# Schem.net
KiCad netlist of a schematic drawn in EAGLE
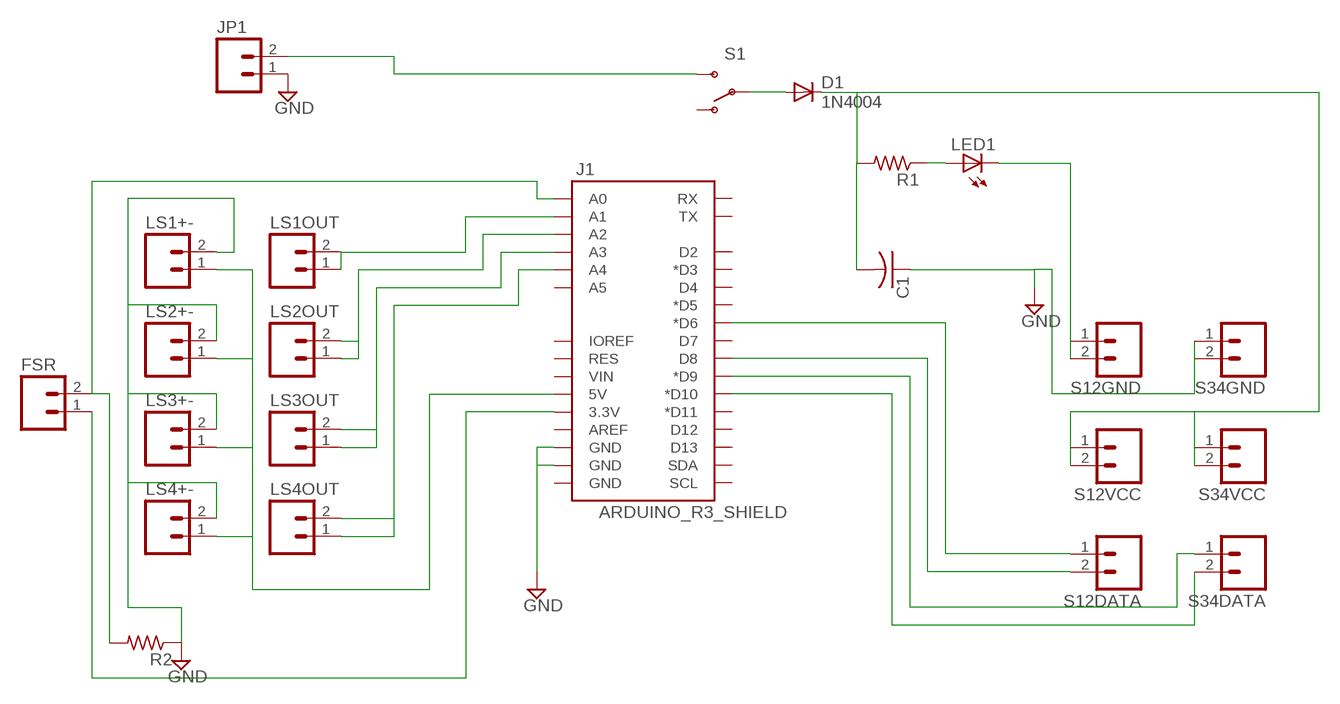
[diagram p0: schematic, sheet 1]

(export (version "E")
  (design (tool "Eeschema 10.0.6"))
  (components
    (comp (ref "C1")
      (value "C-US075-063X106")
      (footprint "eagle-import:C075-063X106")
      (libsource (lib "eagle-import") (part "C-US075-063X106"))
    )
    (comp (ref "D1")
      (value "1N4004")
      (footprint "eagle-import:DO41-10")
      (libsource (lib "eagle-import") (part "1N4004"))
    )
    (comp (ref "FSR")
      (value "M02LOCK")
      (footprint "eagle-import:1X02_LOCK")
      (libsource (lib "eagle-import") (part "M02LOCK"))
    )
    (comp (ref "J1")
      (value "ARDUINO_R3_SHIELD")
      (footprint "eagle-import:UNO_R3_SHIELD")
      (libsource (lib "eagle-import") (part "ARDUINO_R3_SHIELD"))
    )
    (comp (ref "JP1")
      (value "M025MM")
      (footprint "eagle-import:SCREWTERMINAL-5MM-2")
      (libsource (lib "eagle-import") (part "M025MM"))
    )
    (comp (ref "LED1")
      (value "LED_ELD260")
      (footprint "eagle-import:LED_LD260")
      (libsource (lib "eagle-import") (part "LED_ELD260"))
    )
    (comp (ref "LS1+-")
      (value "M02LOCK")
      (footprint "eagle-import:1X02_LOCK")
      (libsource (lib "eagle-import") (part "M02LOCK"))
    )
    (comp (ref "LS1OUT")
      (value "M02LOCK")
      (footprint "eagle-import:1X02_LOCK")
      (libsource (lib "eagle-import") (part "M02LOCK"))
    )
    (comp (ref "LS2+-")
      (value "M02LOCK")
      (footprint "eagle-import:1X02_LOCK")
      (libsource (lib "eagle-import") (part "M02LOCK"))
    )
    (comp (ref "LS2OUT")
      (value "M02LOCK")
      (footprint "eagle-import:1X02_LOCK")
      (libsource (lib "eagle-import") (part "M02LOCK"))
    )
    (comp (ref "LS3+-")
      (value "M02LOCK")
      (footprint "eagle-import:1X02_LOCK")
      (libsource (lib "eagle-import") (part "M02LOCK"))
    )
    (comp (ref "LS3OUT")
      (value "M02LOCK")
      (footprint "eagle-import:1X02_LOCK")
      (libsource (lib "eagle-import") (part "M02LOCK"))
    )
    (comp (ref "LS4+-")
      (value "M02LOCK")
      (footprint "eagle-import:1X02_LOCK")
      (libsource (lib "eagle-import") (part "M02LOCK"))
    )
    (comp (ref "LS4OUT")
      (value "M02LOCK")
      (footprint "eagle-import:1X02_LOCK")
      (libsource (lib "eagle-import") (part "M02LOCK"))
    )
    (comp (ref "R1")
      (value "R-US_0309/10")
      (footprint "eagle-import:0309_10")
      (libsource (lib "eagle-import") (part "R-US_0309/10"))
    )
    (comp (ref "R2")
      (value "R-US_0309/10")
      (footprint "eagle-import:0309_10")
      (libsource (lib "eagle-import") (part "R-US_0309/10"))
    )
    (comp (ref "S1")
      (value "SWITCH-SPDTPTH")
      (footprint "eagle-import:SWITCH-SPDT")
      (libsource (lib "eagle-import") (part "SWITCH-SPDTPTH"))
    )
    (comp (ref "S12DATA")
      (value "M02LOCK")
      (footprint "eagle-import:1X02_LOCK")
      (libsource (lib "eagle-import") (part "M02LOCK"))
    )
    (comp (ref "S12GND")
      (value "M02LOCK")
      (footprint "eagle-import:1X02_LOCK")
      (libsource (lib "eagle-import") (part "M02LOCK"))
    )
    (comp (ref "S12VCC")
      (value "M02LOCK")
      (footprint "eagle-import:1X02_LOCK")
      (libsource (lib "eagle-import") (part "M02LOCK"))
    )
    (comp (ref "S34DATA")
      (value "M02LOCK")
      (footprint "eagle-import:1X02_LOCK")
      (libsource (lib "eagle-import") (part "M02LOCK"))
    )
    (comp (ref "S34GND")
      (value "M02LOCK")
      (footprint "eagle-import:1X02_LOCK")
      (libsource (lib "eagle-import") (part "M02LOCK"))
    )
    (comp (ref "S34VCC")
      (value "M02LOCK")
      (footprint "eagle-import:1X02_LOCK")
      (libsource (lib "eagle-import") (part "M02LOCK"))
    )
  )
  (nets
    (net (code "1") (name "GND") (class "Default")
      (node (ref "C1") (pin "1") (pinfunction "1_1") (pintype "passive"))
      (node (ref "J1") (pin "GND@1") (pinfunction "GND_GND@1") (pintype "bidirectional"))
      (node (ref "J1") (pin "GND@2") (pinfunction "GND_GND@2") (pintype "bidirectional"))
      (node (ref "JP1") (pin "1") (pinfunction "1_1") (pintype "passive"))
      (node (ref "LS1+-") (pin "2") (pinfunction "2_2") (pintype "passive"))
      (node (ref "LS2+-") (pin "2") (pinfunction "2_2") (pintype "passive"))
      (node (ref "LS3+-") (pin "2") (pinfunction "2_2") (pintype "passive"))
      (node (ref "LS4+-") (pin "2") (pinfunction "2_2") (pintype "passive"))
      (node (ref "R2") (pin "1") (pinfunction "1_1") (pintype "passive"))
      (node (ref "S34GND") (pin "1") (pinfunction "1_1") (pintype "passive"))
      (node (ref "S34GND") (pin "2") (pinfunction "2_2") (pintype "passive"))
    )
    (net (code "2") (name "Net-(C1-Pad2)") (class "Default")
      (node (ref "C1") (pin "2") (pinfunction "2_2") (pintype "passive"))
      (node (ref "D1") (pin "C") (pinfunction "C_C") (pintype "passive"))
      (node (ref "R1") (pin "2") (pinfunction "2_2") (pintype "passive"))
      (node (ref "S12VCC") (pin "2") (pinfunction "2_2") (pintype "passive"))
      (node (ref "S34VCC") (pin "1") (pinfunction "1_1") (pintype "passive"))
      (node (ref "S34VCC") (pin "2") (pinfunction "2_2") (pintype "passive"))
    )
    (net (code "3") (name "Net-(FSR-Pad1)") (class "Default")
      (node (ref "FSR") (pin "1") (pinfunction "1_1") (pintype "passive"))
      (node (ref "J1") (pin "3.3V") (pinfunction "3.3V_3.3V") (pintype "bidirectional"))
    )
    (net (code "4") (name "Net-(FSR-Pad2)") (class "Default")
      (node (ref "FSR") (pin "2") (pinfunction "2_2") (pintype "passive"))
      (node (ref "J1") (pin "A0") (pinfunction "A0_A0") (pintype "bidirectional"))
      (node (ref "R2") (pin "2") (pinfunction "2_2") (pintype "passive"))
    )
    (net (code "5") (name "Net-(J1-*D6)") (class "Default")
      (node (ref "J1") (pin "D6") (pinfunction "*D6_D6") (pintype "bidirectional"))
      (node (ref "S12DATA") (pin "1") (pinfunction "1_1") (pintype "passive"))
    )
    (net (code "6") (name "Net-(J1-*D9)") (class "Default")
      (node (ref "J1") (pin "D9") (pinfunction "*D9_D9") (pintype "bidirectional"))
      (node (ref "S34DATA") (pin "1") (pinfunction "1_1") (pintype "passive"))
    )
    (net (code "7") (name "Net-(J1-*D10)") (class "Default")
      (node (ref "J1") (pin "D10") (pinfunction "*D10_D10") (pintype "bidirectional"))
      (node (ref "S34DATA") (pin "2") (pinfunction "2_2") (pintype "passive"))
    )
    (net (code "8") (name "Net-(J1-Pad5V)") (class "Default")
      (node (ref "J1") (pin "5V") (pinfunction "5V_5V") (pintype "bidirectional"))
      (node (ref "LS1+-") (pin "1") (pinfunction "1_1") (pintype "passive"))
      (node (ref "LS2+-") (pin "1") (pinfunction "1_1") (pintype "passive"))
      (node (ref "LS3+-") (pin "1") (pinfunction "1_1") (pintype "passive"))
      (node (ref "LS4+-") (pin "1") (pinfunction "1_1") (pintype "passive"))
    )
    (net (code "9") (name "Net-(J1-PadA1)") (class "Default")
      (node (ref "J1") (pin "A1") (pinfunction "A1_A1") (pintype "bidirectional"))
      (node (ref "LS1OUT") (pin "1") (pinfunction "1_1") (pintype "passive"))
      (node (ref "LS1OUT") (pin "2") (pinfunction "2_2") (pintype "passive"))
    )
    (net (code "10") (name "Net-(J1-PadA2)") (class "Default")
      (node (ref "J1") (pin "A2") (pinfunction "A2_A2") (pintype "bidirectional"))
      (node (ref "LS2OUT") (pin "1") (pinfunction "1_1") (pintype "passive"))
      (node (ref "LS2OUT") (pin "2") (pinfunction "2_2") (pintype "passive"))
    )
    (net (code "11") (name "Net-(J1-PadA3)") (class "Default")
      (node (ref "J1") (pin "A3") (pinfunction "A3_A3") (pintype "bidirectional"))
      (node (ref "LS3OUT") (pin "1") (pinfunction "1_1") (pintype "passive"))
      (node (ref "LS3OUT") (pin "2") (pinfunction "2_2") (pintype "passive"))
    )
    (net (code "12") (name "Net-(J1-PadA4)") (class "Default")
      (node (ref "J1") (pin "A4") (pinfunction "A4_A4") (pintype "bidirectional"))
      (node (ref "LS4OUT") (pin "1") (pinfunction "1_1") (pintype "passive"))
      (node (ref "LS4OUT") (pin "2") (pinfunction "2_2") (pintype "passive"))
    )
    (net (code "13") (name "Net-(J1-PadD8)") (class "Default")
      (node (ref "J1") (pin "D8") (pinfunction "D8_D8") (pintype "bidirectional"))
      (node (ref "S12DATA") (pin "2") (pinfunction "2_2") (pintype "passive"))
    )
    (net (code "14") (name "Net-(LED1-C)") (class "Default")
      (node (ref "LED1") (pin "K") (pinfunction "C_K") (pintype "passive"))
      (node (ref "S12GND") (pin "1") (pinfunction "1_1") (pintype "passive"))
      (node (ref "S12GND") (pin "2") (pinfunction "2_2") (pintype "passive"))
    )
    (net (code "15") (name "Net-(LED1-PadA)") (class "Default")
      (node (ref "LED1") (pin "A") (pinfunction "A_A") (pintype "passive"))
      (node (ref "R1") (pin "1") (pinfunction "1_1") (pintype "passive"))
    )
    (net (code "16") (name "Net-(S1-P)") (class "Default")
      (node (ref "D1") (pin "A") (pinfunction "A_A") (pintype "passive"))
      (node (ref "S1") (pin "2") (pinfunction "P_2") (pintype "passive"))
    )
    (net (code "17") (name "Net-(S1-S)") (class "Default")
      (node (ref "JP1") (pin "2") (pinfunction "2_2") (pintype "passive"))
      (node (ref "S1") (pin "3") (pinfunction "S_3") (pintype "passive"))
    )
    (net (code "18") (name "unconnected-(J1-*D3-PadD3)") (class "Default")
      (node (ref "J1") (pin "D3") (pinfunction "*D3_D3") (pintype "bidirectional"))
    )
    (net (code "19") (name "unconnected-(J1-*D5-PadD5)") (class "Default")
      (node (ref "J1") (pin "D5") (pinfunction "*D5_D5") (pintype "bidirectional"))
    )
    (net (code "20") (name "unconnected-(J1-*D11-PadD11)") (class "Default")
      (node (ref "J1") (pin "D11") (pinfunction "*D11_D11") (pintype "bidirectional"))
    )
    (net (code "21") (name "unconnected-(J1-GND-PadGND@0)") (class "Default")
      (node (ref "J1") (pin "GND@0") (pinfunction "GND_GND@0") (pintype "bidirectional"))
    )
    (net (code "22") (name "unconnected-(J1-PadA5)") (class "Default")
      (node (ref "J1") (pin "A5") (pinfunction "A5_A5") (pintype "bidirectional"))
    )
    (net (code "23") (name "unconnected-(J1-PadAREF)") (class "Default")
      (node (ref "J1") (pin "AREF") (pinfunction "AREF_AREF") (pintype "bidirectional"))
    )
    (net (code "24") (name "unconnected-(J1-PadD2)") (class "Default")
      (node (ref "J1") (pin "D2") (pinfunction "D2_D2") (pintype "bidirectional"))
    )
    (net (code "25") (name "unconnected-(J1-PadD4)") (class "Default")
      (node (ref "J1") (pin "D4") (pinfunction "D4_D4") (pintype "bidirectional"))
    )
    (net (code "26") (name "unconnected-(J1-PadD7)") (class "Default")
      (node (ref "J1") (pin "D7") (pinfunction "D7_D7") (pintype "bidirectional"))
    )
    (net (code "27") (name "unconnected-(J1-PadD12)") (class "Default")
      (node (ref "J1") (pin "D12") (pinfunction "D12_D12") (pintype "bidirectional"))
    )
    (net (code "28") (name "unconnected-(J1-PadD13)") (class "Default")
      (node (ref "J1") (pin "D13") (pinfunction "D13_D13") (pintype "bidirectional"))
    )
    (net (code "29") (name "unconnected-(J1-PadIOREF)") (class "Default")
      (node (ref "J1") (pin "IOREF") (pinfunction "IOREF_IOREF") (pintype "bidirectional"))
    )
    (net (code "30") (name "unconnected-(J1-PadRES)") (class "Default")
      (node (ref "J1") (pin "RES") (pinfunction "RES_RES") (pintype "bidirectional"))
    )
    (net (code "31") (name "unconnected-(J1-PadRX)") (class "Default")
      (node (ref "J1") (pin "RX") (pinfunction "RX_RX") (pintype "bidirectional"))
    )
    (net (code "32") (name "unconnected-(J1-PadSCL)") (class "Default")
      (node (ref "J1") (pin "SCL") (pinfunction "SCL_SCL") (pintype "bidirectional"))
    )
    (net (code "33") (name "unconnected-(J1-PadSDA)") (class "Default")
      (node (ref "J1") (pin "SDA") (pinfunction "SDA_SDA") (pintype "bidirectional"))
    )
    (net (code "34") (name "unconnected-(J1-PadTX)") (class "Default")
      (node (ref "J1") (pin "TX") (pinfunction "TX_TX") (pintype "bidirectional"))
    )
    (net (code "35") (name "unconnected-(J1-PadVIN)") (class "Default")
      (node (ref "J1") (pin "VIN") (pinfunction "VIN_VIN") (pintype "bidirectional"))
    )
    (net (code "36") (name "unconnected-(S1-O-Pad1)") (class "Default")
      (node (ref "S1") (pin "1") (pinfunction "O_1") (pintype "passive"))
    )
    (net (code "37") (name "unconnected-(S12VCC-Pad1)") (class "Default")
      (node (ref "S12VCC") (pin "1") (pinfunction "1_1") (pintype "passive"))
    )
  )
)
